# Main_Schematic.net
KiCad netlist of a schematic drawn in Altium Designer
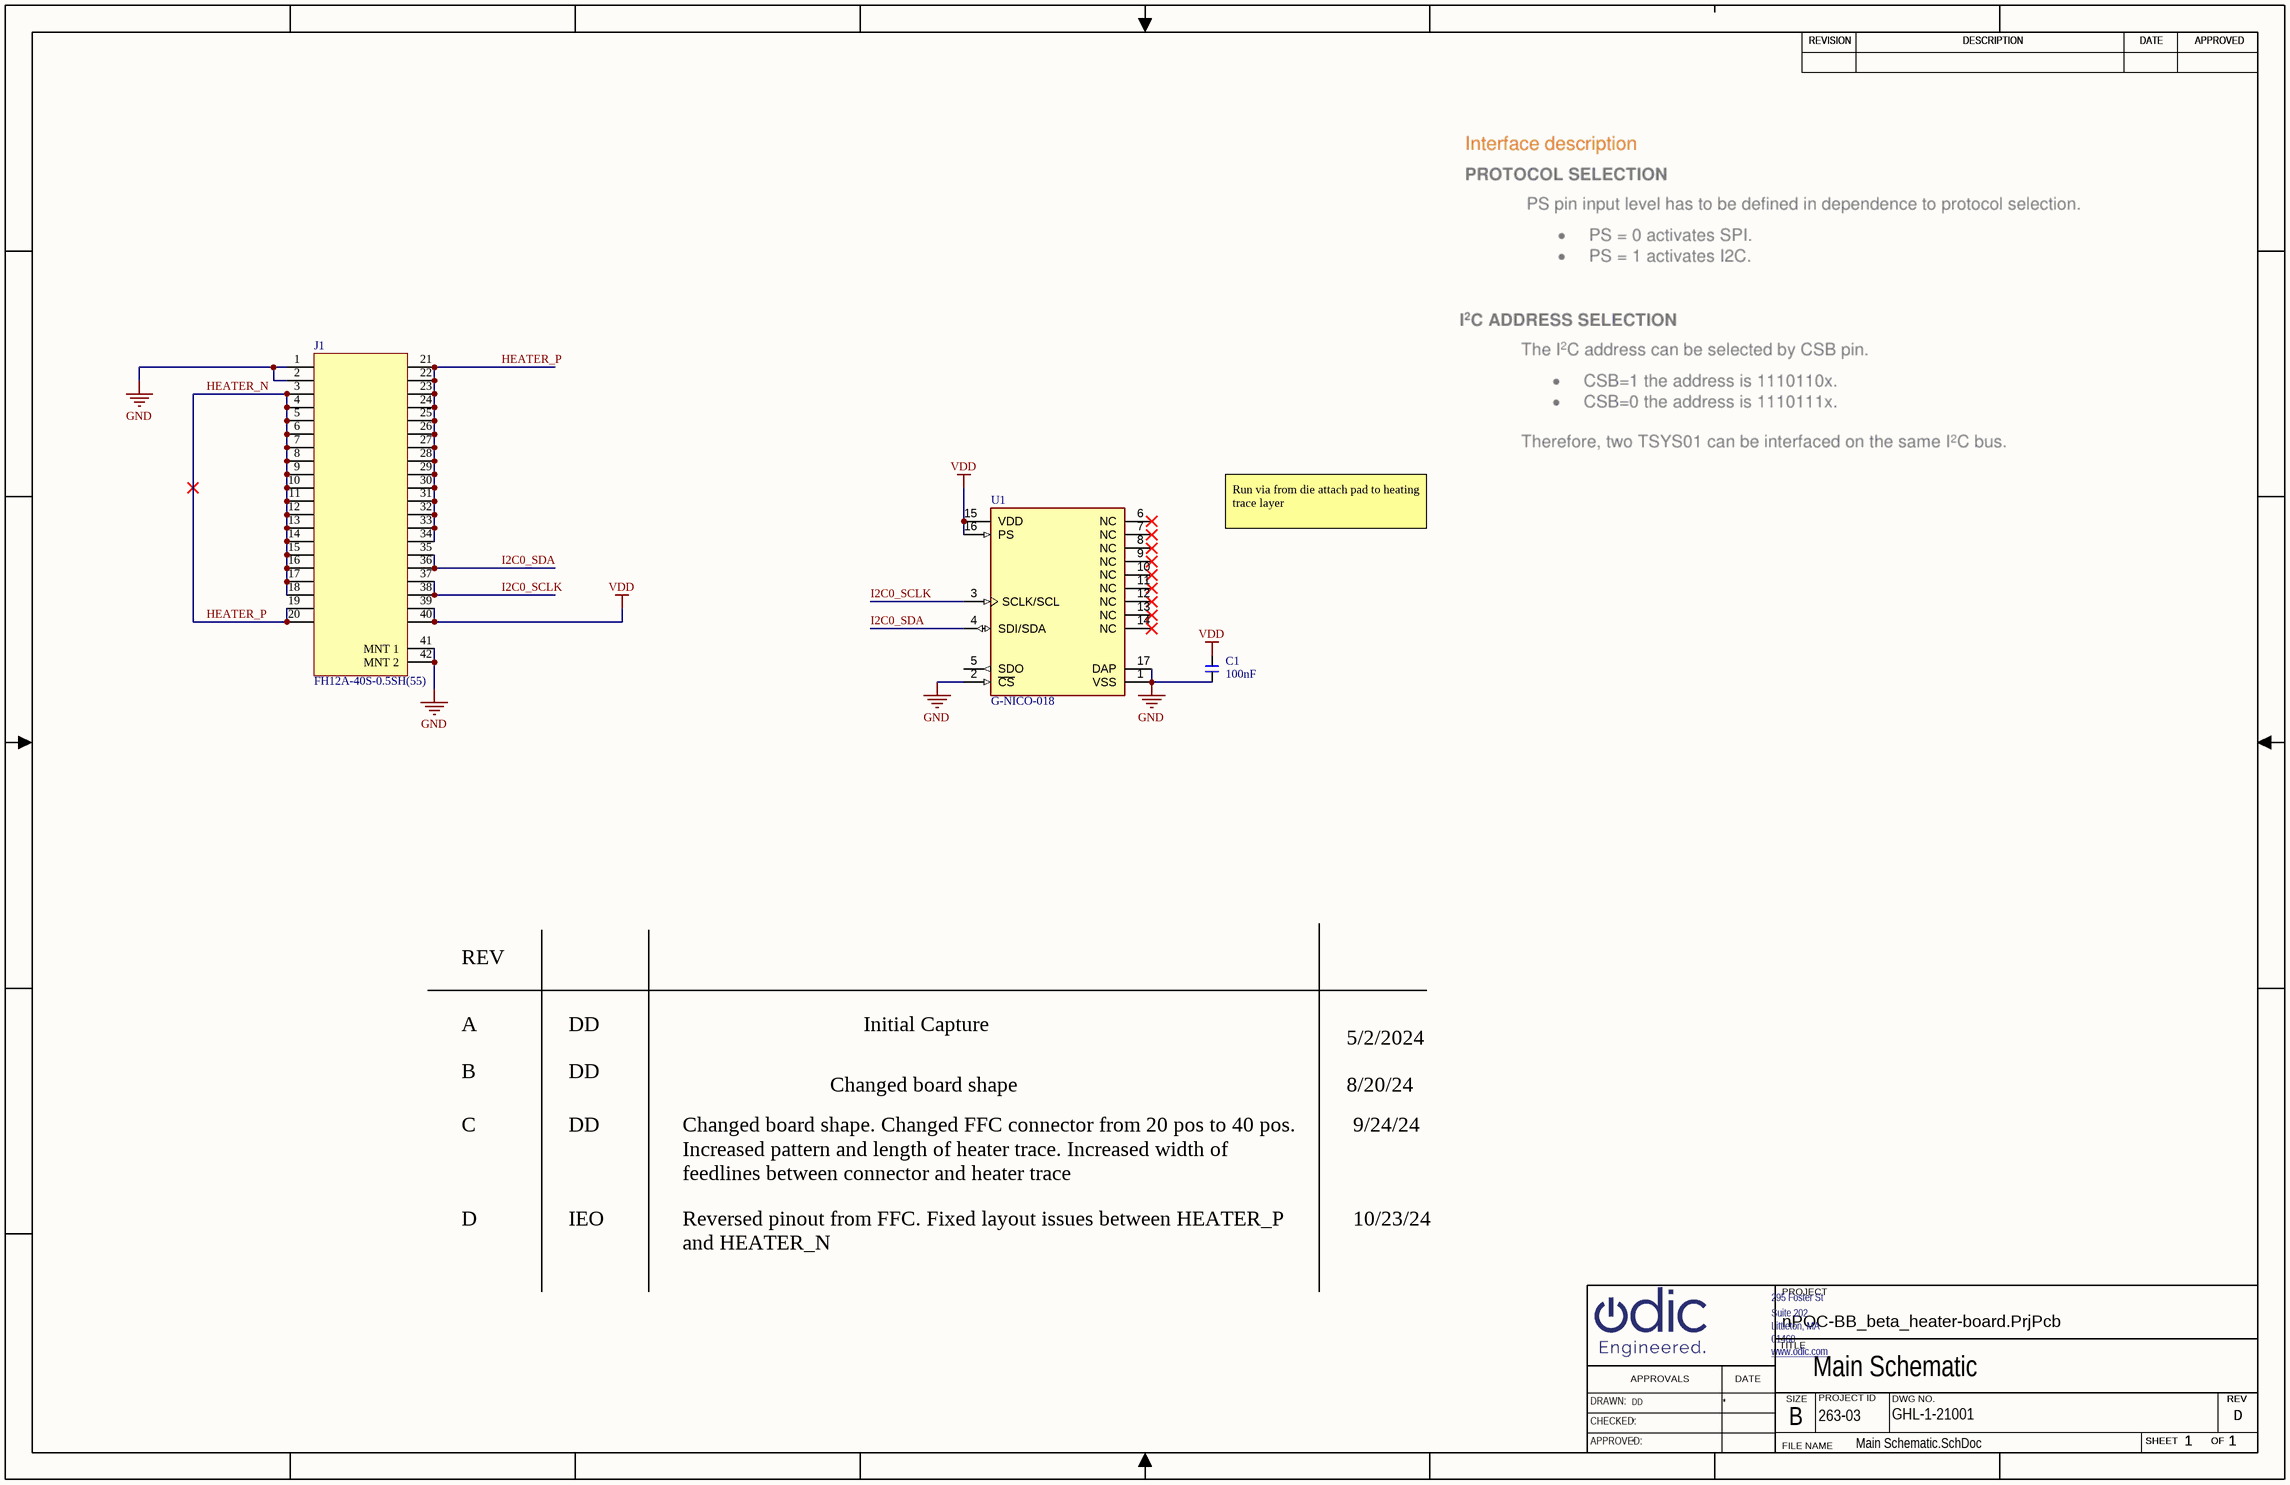
[diagram p0: Main Schematic.SchDoc]

(export (version "E")
  (design (tool "Eeschema 10.0.6"))
  (components
    (comp (ref "C1")
      (value "100nF")
      (footprint "C0402")
      (description "Ceramic capacitor SMD 0402 100nF 16V X7R 10%")
      (fields (field (name "VOLTAGE") "16V") (field (name "TOLERANCE") "10%"))
      (libsource (lib "Odic Inc") (part "cAP"))
    )
    (comp (ref "J1")
      (value "FH12A-40S-0.5SH(55)")
      (footprint "hirose_fh12a-40s-0p5sh55")
      (description "Conn Ffc/fpc Connector Skt 40 Pos 0.5MM Solder Ra SMD T/r / Conn Ffc Top 40POS 0.50MM R/a")
      (libsource (lib "Odic Inc") (part "FH12A-40S-0.5SH(55)-Symbol"))
    )
    (comp (ref "U1")
      (value "G-NICO-018")
      (footprint "QFN16_4X4_P65mm")
      (description "TSYS01 Series 3.6 V -40 to +125 SMT Digital Temperature Sensor - QFN-16")
      (libsource (lib "Odic Inc") (part "cde510fbdee2f3b7ede55338efd2f6c"))
    )
  )
  (nets
    (net (code "1") (name "/HEATER_N") (class "Default")
      (node (ref "J1") (pin "10") (pinfunction "10_10") (pintype "passive"))
      (node (ref "J1") (pin "11") (pinfunction "11_11") (pintype "passive"))
      (node (ref "J1") (pin "12") (pinfunction "12_12") (pintype "passive"))
      (node (ref "J1") (pin "13") (pinfunction "13_13") (pintype "passive"))
      (node (ref "J1") (pin "14") (pinfunction "14_14") (pintype "passive"))
      (node (ref "J1") (pin "15") (pinfunction "15_15") (pintype "passive"))
      (node (ref "J1") (pin "16") (pinfunction "16_16") (pintype "passive"))
      (node (ref "J1") (pin "17") (pinfunction "17_17") (pintype "passive"))
      (node (ref "J1") (pin "18") (pinfunction "18_18") (pintype "passive"))
      (node (ref "J1") (pin "19") (pinfunction "19_19") (pintype "passive"))
      (node (ref "J1") (pin "20") (pinfunction "20_20") (pintype "passive"))
      (node (ref "J1") (pin "21") (pinfunction "21_21") (pintype "passive"))
      (node (ref "J1") (pin "22") (pinfunction "22_22") (pintype "passive"))
      (node (ref "J1") (pin "23") (pinfunction "23_23") (pintype "passive"))
      (node (ref "J1") (pin "24") (pinfunction "24_24") (pintype "passive"))
      (node (ref "J1") (pin "25") (pinfunction "25_25") (pintype "passive"))
      (node (ref "J1") (pin "26") (pinfunction "26_26") (pintype "passive"))
      (node (ref "J1") (pin "27") (pinfunction "27_27") (pintype "passive"))
      (node (ref "J1") (pin "28") (pinfunction "28_28") (pintype "passive"))
      (node (ref "J1") (pin "29") (pinfunction "29_29") (pintype "passive"))
      (node (ref "J1") (pin "3") (pinfunction "3_3") (pintype "passive"))
      (node (ref "J1") (pin "30") (pinfunction "30_30") (pintype "passive"))
      (node (ref "J1") (pin "31") (pinfunction "31_31") (pintype "passive"))
      (node (ref "J1") (pin "32") (pinfunction "32_32") (pintype "passive"))
      (node (ref "J1") (pin "33") (pinfunction "33_33") (pintype "passive"))
      (node (ref "J1") (pin "34") (pinfunction "34_34") (pintype "passive"))
      (node (ref "J1") (pin "4") (pinfunction "4_4") (pintype "passive"))
      (node (ref "J1") (pin "5") (pinfunction "5_5") (pintype "passive"))
      (node (ref "J1") (pin "6") (pinfunction "6_6") (pintype "passive"))
      (node (ref "J1") (pin "7") (pinfunction "7_7") (pintype "passive"))
      (node (ref "J1") (pin "8") (pinfunction "8_8") (pintype "passive"))
      (node (ref "J1") (pin "9") (pinfunction "9_9") (pintype "passive"))
    )
    (net (code "2") (name "/I2C0_SCLK") (class "Default")
      (node (ref "J1") (pin "37") (pinfunction "37_37") (pintype "passive"))
      (node (ref "J1") (pin "38") (pinfunction "38_38") (pintype "passive"))
      (node (ref "U1") (pin "3") (pinfunction "SCLK/SCL_3") (pintype "input"))
    )
    (net (code "3") (name "/I2C0_SDA") (class "Default")
      (node (ref "J1") (pin "35") (pinfunction "35_35") (pintype "passive"))
      (node (ref "J1") (pin "36") (pinfunction "36_36") (pintype "passive"))
      (node (ref "U1") (pin "4") (pinfunction "SDI/SDA_4") (pintype "bidirectional"))
    )
    (net (code "4") (name "GND") (class "Default")
      (node (ref "C1") (pin "1") (pinfunction "1_1") (pintype "passive"))
      (node (ref "J1") (pin "1") (pinfunction "1_1") (pintype "passive"))
      (node (ref "J1") (pin "2") (pinfunction "2_2") (pintype "passive"))
      (node (ref "J1") (pin "41") (pinfunction "MNT_1_41") (pintype "passive"))
      (node (ref "J1") (pin "42") (pinfunction "MNT_2_42") (pintype "passive"))
      (node (ref "U1") (pin "1") (pinfunction "VSS_1") (pintype "power_in"))
      (node (ref "U1") (pin "17") (pinfunction "DAP_17") (pintype "power_in"))
      (node (ref "U1") (pin "2") (pinfunction "~{CS}_2") (pintype "input"))
    )
    (net (code "5") (name "VDD") (class "Default")
      (node (ref "C1") (pin "2") (pinfunction "2_2") (pintype "passive"))
      (node (ref "J1") (pin "39") (pinfunction "39_39") (pintype "passive"))
      (node (ref "J1") (pin "40") (pinfunction "40_40") (pintype "passive"))
      (node (ref "U1") (pin "15") (pinfunction "VDD_15") (pintype "power_in"))
      (node (ref "U1") (pin "16") (pinfunction "PS_16") (pintype "input"))
    )
    (net (code "6") (name "unconnected-(U1-NC-Pad6)") (class "Default")
      (node (ref "U1") (pin "6") (pinfunction "NC_6") (pintype "passive+no_connect"))
    )
    (net (code "7") (name "unconnected-(U1-NC-Pad7)") (class "Default")
      (node (ref "U1") (pin "7") (pinfunction "NC_7") (pintype "passive+no_connect"))
    )
    (net (code "8") (name "unconnected-(U1-NC-Pad8)") (class "Default")
      (node (ref "U1") (pin "8") (pinfunction "NC_8") (pintype "passive+no_connect"))
    )
    (net (code "9") (name "unconnected-(U1-NC-Pad9)") (class "Default")
      (node (ref "U1") (pin "9") (pinfunction "NC_9") (pintype "passive+no_connect"))
    )
    (net (code "10") (name "unconnected-(U1-NC-Pad10)") (class "Default")
      (node (ref "U1") (pin "10") (pinfunction "NC_10") (pintype "passive+no_connect"))
    )
    (net (code "11") (name "unconnected-(U1-NC-Pad11)") (class "Default")
      (node (ref "U1") (pin "11") (pinfunction "NC_11") (pintype "passive+no_connect"))
    )
    (net (code "12") (name "unconnected-(U1-NC-Pad12)") (class "Default")
      (node (ref "U1") (pin "12") (pinfunction "NC_12") (pintype "passive+no_connect"))
    )
    (net (code "13") (name "unconnected-(U1-NC-Pad13)") (class "Default")
      (node (ref "U1") (pin "13") (pinfunction "NC_13") (pintype "passive+no_connect"))
    )
    (net (code "14") (name "unconnected-(U1-NC-Pad14)") (class "Default")
      (node (ref "U1") (pin "14") (pinfunction "NC_14") (pintype "passive+no_connect"))
    )
    (net (code "15") (name "unconnected-(U1-SDO-Pad5)") (class "Default")
      (node (ref "U1") (pin "5") (pinfunction "SDO_5") (pintype "output"))
    )
  )
)
